# Section_A_-_Title_A.net
KiCad netlist of a schematic drawn in Altium Designer
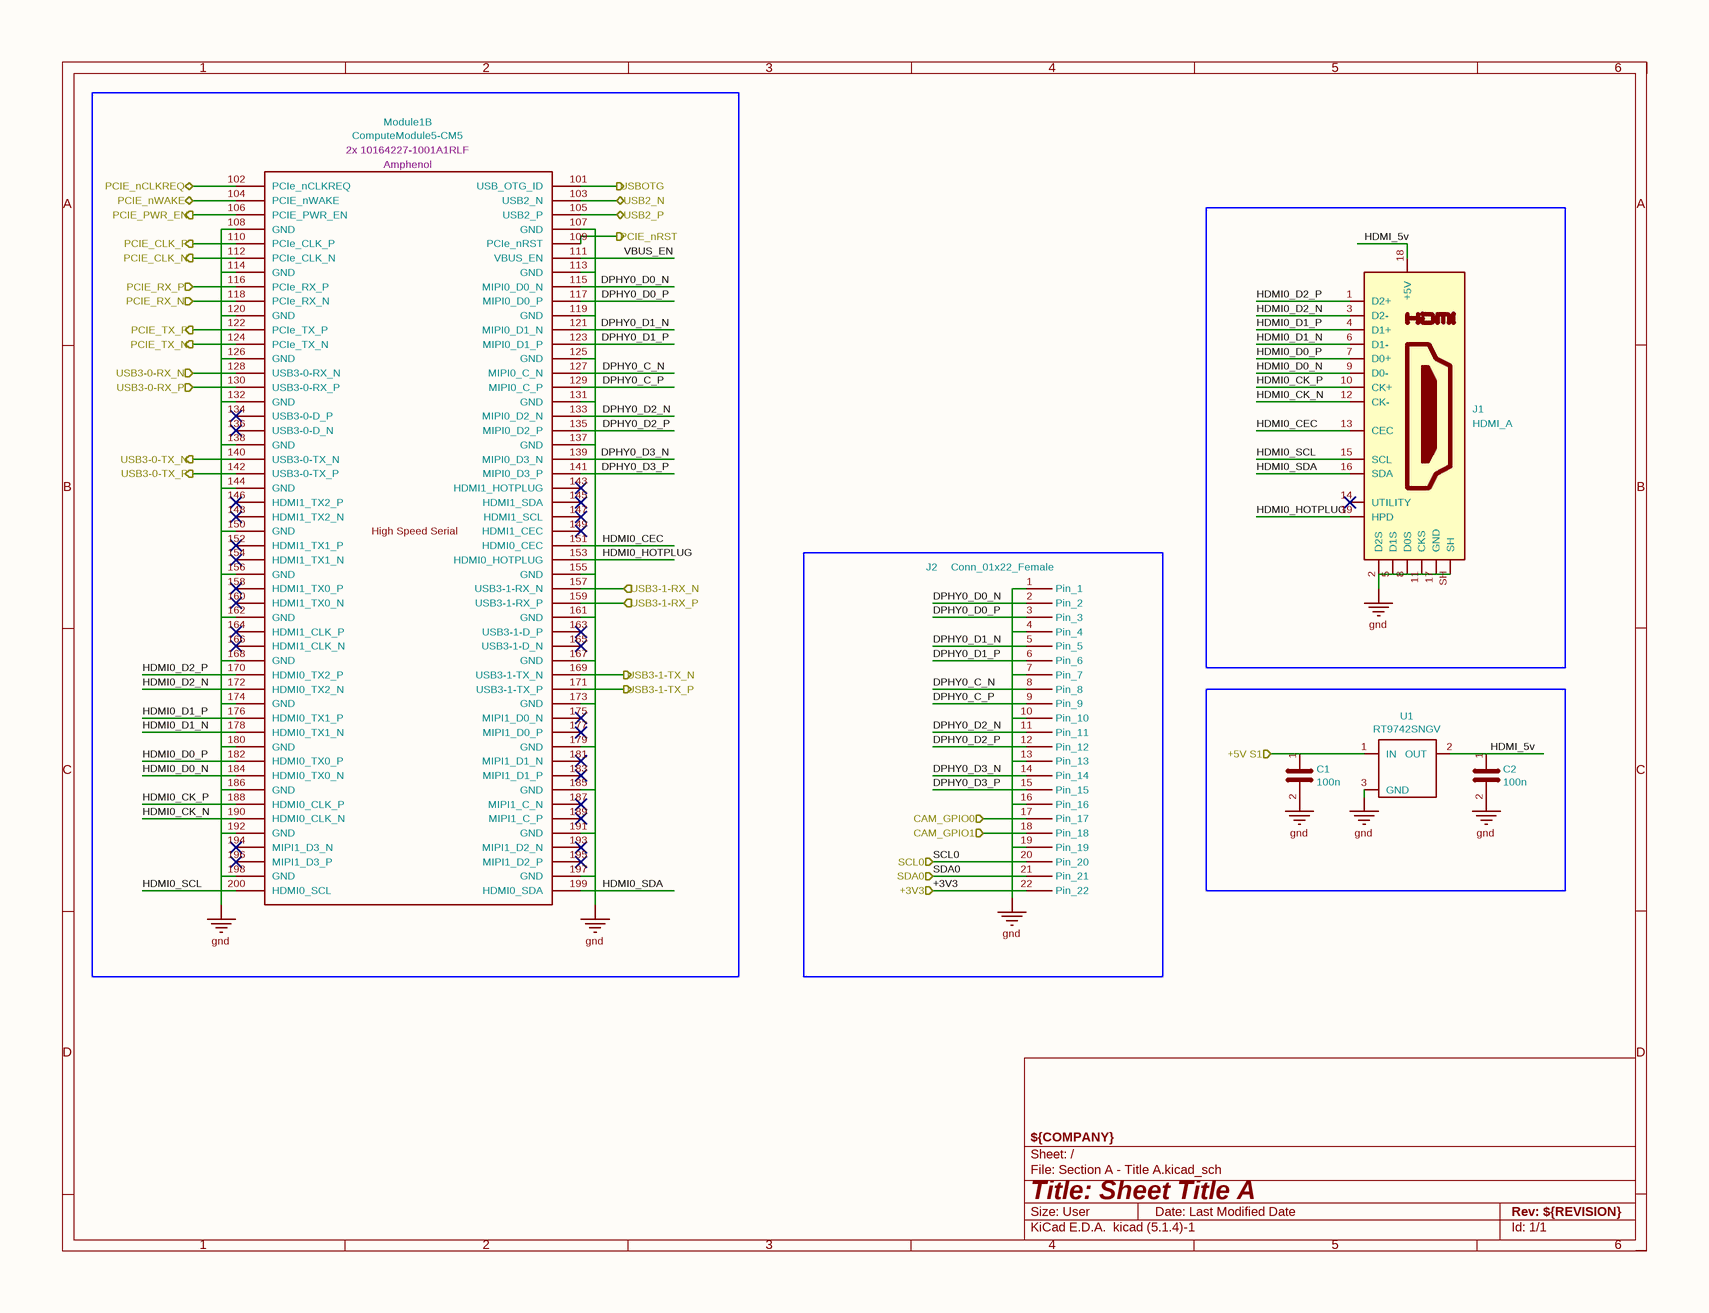
[diagram p0: Section A - Title A.SchDoc]

(export (version "E")
  (design (tool "Eeschema 10.0.6"))
  (components
    (comp (ref "C1") (value "100n") (libsource (lib "Device") (part "C")))
    (comp (ref "C2") (value "100n") (libsource (lib "Device") (part "C")))
    (comp (ref "J1")
      (value "HDMI_A")
      (description "HDMI type A connector")
      (libsource (lib "Connector") (part "HDMI_A"))
    )
    (comp (ref "J2") (value "Conn_01x22_Female") (libsource (lib "Connector") (part "Conn_01x22_Socket")))
    (comp (ref "Module1")
      (value "ComputeModule5-CM5")
      (description "RaspberryPi Compute module 5")
      (fields (field (name "FIELD4") "Amphenol") (field (name "FIELD5") "2x 10164227-1001A1RLF"))
      (libsource (lib "CM5IO") (part "ComputeModule5-CM5"))
    )
    (comp (ref "U1") (value "RT9742SNGV") (libsource (lib "CM5IO") (part "RT9742SNGV")))
  )
  (nets
    (net (code "1") (name "/+3V3") (class "Default")
      (node (ref "J2") (pin "22") (pinfunction "Pin_22_22") (pintype "passive"))
    )
    (net (code "2") (name "/+5V S1") (class "Default")
      (node (ref "C1") (pin "1") (pinfunction "1_1") (pintype "passive"))
      (node (ref "U1") (pin "1") (pinfunction "IN_1") (pintype "passive"))
    )
    (net (code "3") (name "/CAM_GPIO0") (class "Default")
      (node (ref "J2") (pin "17") (pinfunction "Pin_17_17") (pintype "passive"))
    )
    (net (code "4") (name "/CAM_GPIO1") (class "Default")
      (node (ref "J2") (pin "18") (pinfunction "Pin_18_18") (pintype "passive"))
    )
    (net (code "5") (name "/DPHY0_C_N") (class "Default")
      (node (ref "J2") (pin "8") (pinfunction "Pin_8_8") (pintype "passive"))
      (node (ref "Module1") (pin "127") (pinfunction "MIPI0_C_N_127") (pintype "passive"))
    )
    (net (code "6") (name "/DPHY0_C_P") (class "Default")
      (node (ref "J2") (pin "9") (pinfunction "Pin_9_9") (pintype "passive"))
      (node (ref "Module1") (pin "129") (pinfunction "MIPI0_C_P_129") (pintype "passive"))
    )
    (net (code "7") (name "/DPHY0_D0_N") (class "Default")
      (node (ref "J2") (pin "2") (pinfunction "Pin_2_2") (pintype "passive"))
      (node (ref "Module1") (pin "115") (pinfunction "MIPI0_D0_N_115") (pintype "passive"))
    )
    (net (code "8") (name "/DPHY0_D0_P") (class "Default")
      (node (ref "J2") (pin "3") (pinfunction "Pin_3_3") (pintype "passive"))
      (node (ref "Module1") (pin "117") (pinfunction "MIPI0_D0_P_117") (pintype "passive"))
    )
    (net (code "9") (name "/DPHY0_D1_N") (class "Default")
      (node (ref "J2") (pin "5") (pinfunction "Pin_5_5") (pintype "passive"))
      (node (ref "Module1") (pin "121") (pinfunction "MIPI0_D1_N_121") (pintype "passive"))
    )
    (net (code "10") (name "/DPHY0_D1_P") (class "Default")
      (node (ref "J2") (pin "6") (pinfunction "Pin_6_6") (pintype "passive"))
      (node (ref "Module1") (pin "123") (pinfunction "MIPI0_D1_P_123") (pintype "passive"))
    )
    (net (code "11") (name "/DPHY0_D2_N") (class "Default")
      (node (ref "J2") (pin "11") (pinfunction "Pin_11_11") (pintype "passive"))
      (node (ref "Module1") (pin "133") (pinfunction "MIPI0_D2_N_133") (pintype "passive"))
    )
    (net (code "12") (name "/DPHY0_D2_P") (class "Default")
      (node (ref "J2") (pin "12") (pinfunction "Pin_12_12") (pintype "passive"))
      (node (ref "Module1") (pin "135") (pinfunction "MIPI0_D2_P_135") (pintype "passive"))
    )
    (net (code "13") (name "/DPHY0_D3_N") (class "Default")
      (node (ref "J2") (pin "14") (pinfunction "Pin_14_14") (pintype "passive"))
      (node (ref "Module1") (pin "139") (pinfunction "MIPI0_D3_N_139") (pintype "passive"))
    )
    (net (code "14") (name "/DPHY0_D3_P") (class "Default")
      (node (ref "J2") (pin "15") (pinfunction "Pin_15_15") (pintype "passive"))
      (node (ref "Module1") (pin "141") (pinfunction "MIPI0_D3_P_141") (pintype "passive"))
    )
    (net (code "15") (name "/HDMI0_CEC") (class "Default")
      (node (ref "J1") (pin "13") (pinfunction "CEC_13") (pintype "passive"))
      (node (ref "Module1") (pin "151") (pinfunction "HDMI0_CEC_151") (pintype "passive"))
    )
    (net (code "16") (name "/HDMI0_CK_N") (class "Default")
      (node (ref "J1") (pin "12") (pinfunction "CK-_12") (pintype "passive"))
      (node (ref "Module1") (pin "190") (pinfunction "HDMI0_CLK_N_190") (pintype "passive"))
    )
    (net (code "17") (name "/HDMI0_CK_P") (class "Default")
      (node (ref "J1") (pin "10") (pinfunction "CK+_10") (pintype "passive"))
      (node (ref "Module1") (pin "188") (pinfunction "HDMI0_CLK_P_188") (pintype "passive"))
    )
    (net (code "18") (name "/HDMI0_D0_N") (class "Default")
      (node (ref "J1") (pin "9") (pinfunction "D0-_9") (pintype "passive"))
      (node (ref "Module1") (pin "184") (pinfunction "HDMI0_TX0_N_184") (pintype "passive"))
    )
    (net (code "19") (name "/HDMI0_D0_P") (class "Default")
      (node (ref "J1") (pin "7") (pinfunction "D0+_7") (pintype "passive"))
      (node (ref "Module1") (pin "182") (pinfunction "HDMI0_TX0_P_182") (pintype "passive"))
    )
    (net (code "20") (name "/HDMI0_D1_N") (class "Default")
      (node (ref "J1") (pin "6") (pinfunction "D1-_6") (pintype "passive"))
      (node (ref "Module1") (pin "178") (pinfunction "HDMI0_TX1_N_178") (pintype "passive"))
    )
    (net (code "21") (name "/HDMI0_D1_P") (class "Default")
      (node (ref "J1") (pin "4") (pinfunction "D1+_4") (pintype "passive"))
      (node (ref "Module1") (pin "176") (pinfunction "HDMI0_TX1_P_176") (pintype "passive"))
    )
    (net (code "22") (name "/HDMI0_D2_N") (class "Default")
      (node (ref "J1") (pin "3") (pinfunction "D2-_3") (pintype "passive"))
      (node (ref "Module1") (pin "172") (pinfunction "HDMI0_TX2_N_172") (pintype "passive"))
    )
    (net (code "23") (name "/HDMI0_D2_P") (class "Default")
      (node (ref "J1") (pin "1") (pinfunction "D2+_1") (pintype "passive"))
      (node (ref "Module1") (pin "170") (pinfunction "HDMI0_TX2_P_170") (pintype "passive"))
    )
    (net (code "24") (name "/HDMI0_HOTPLUG") (class "Default")
      (node (ref "J1") (pin "19") (pinfunction "HPD_19") (pintype "passive"))
      (node (ref "Module1") (pin "153") (pinfunction "HDMI0_HOTPLUG_153") (pintype "passive"))
    )
    (net (code "25") (name "/HDMI0_SCL") (class "Default")
      (node (ref "J1") (pin "15") (pinfunction "SCL_15") (pintype "passive"))
      (node (ref "Module1") (pin "200") (pinfunction "HDMI0_SCL_200") (pintype "passive"))
    )
    (net (code "26") (name "/HDMI0_SDA") (class "Default")
      (node (ref "J1") (pin "16") (pinfunction "SDA_16") (pintype "passive"))
      (node (ref "Module1") (pin "199") (pinfunction "HDMI0_SDA_199") (pintype "passive"))
    )
    (net (code "27") (name "/HDMI_5v") (class "Default")
      (node (ref "C2") (pin "1") (pinfunction "1_1") (pintype "passive"))
      (node (ref "J1") (pin "18") (pinfunction "+5V_18") (pintype "passive"))
      (node (ref "U1") (pin "2") (pinfunction "OUT_2") (pintype "passive"))
    )
    (net (code "28") (name "/PCIE_CLK_N") (class "Default")
      (node (ref "Module1") (pin "112") (pinfunction "PCIe_CLK_N_112") (pintype "passive"))
    )
    (net (code "29") (name "/PCIE_CLK_P") (class "Default")
      (node (ref "Module1") (pin "110") (pinfunction "PCIe_CLK_P_110") (pintype "passive"))
    )
    (net (code "30") (name "/PCIE_PWR_EN") (class "Default")
      (node (ref "Module1") (pin "106") (pinfunction "PCIE_PWR_EN_106") (pintype "passive"))
    )
    (net (code "31") (name "/PCIE_RX_N") (class "Default")
      (node (ref "Module1") (pin "118") (pinfunction "PCIe_RX_N_118") (pintype "passive"))
    )
    (net (code "32") (name "/PCIE_RX_P") (class "Default")
      (node (ref "Module1") (pin "116") (pinfunction "PCIe_RX_P_116") (pintype "passive"))
    )
    (net (code "33") (name "/PCIE_TX_N") (class "Default")
      (node (ref "Module1") (pin "124") (pinfunction "PCIe_TX_N_124") (pintype "passive"))
    )
    (net (code "34") (name "/PCIE_TX_P") (class "Default")
      (node (ref "Module1") (pin "122") (pinfunction "PCIe_TX_P_122") (pintype "passive"))
    )
    (net (code "35") (name "/PCIE_nCLKREQ") (class "Default")
      (node (ref "Module1") (pin "102") (pinfunction "PCIe_nCLKREQ_102") (pintype "passive"))
    )
    (net (code "36") (name "/PCIE_nRST") (class "Default")
      (node (ref "Module1") (pin "109") (pinfunction "PCIe_nRST_109") (pintype "passive"))
    )
    (net (code "37") (name "/PCIE_nWAKE") (class "Default")
      (node (ref "Module1") (pin "104") (pinfunction "PCIE_nWAKE_104") (pintype "passive"))
    )
    (net (code "38") (name "/SCL0") (class "Default")
      (node (ref "J2") (pin "20") (pinfunction "Pin_20_20") (pintype "passive"))
    )
    (net (code "39") (name "/SDA0") (class "Default")
      (node (ref "J2") (pin "21") (pinfunction "Pin_21_21") (pintype "passive"))
    )
    (net (code "40") (name "/USB2_N") (class "Default")
      (node (ref "Module1") (pin "103") (pinfunction "USB2_N_103") (pintype "passive"))
    )
    (net (code "41") (name "/USB2_P") (class "Default")
      (node (ref "Module1") (pin "105") (pinfunction "USB2_P_105") (pintype "passive"))
    )
    (net (code "42") (name "/USB3-0-RX_N") (class "Default")
      (node (ref "Module1") (pin "128") (pinfunction "USB3-0-RX_N_128") (pintype "passive"))
    )
    (net (code "43") (name "/USB3-0-RX_P") (class "Default")
      (node (ref "Module1") (pin "130") (pinfunction "USB3-0-RX_P_130") (pintype "passive"))
    )
    (net (code "44") (name "/USB3-0-TX_N") (class "Default")
      (node (ref "Module1") (pin "140") (pinfunction "USB3-0-TX_N_140") (pintype "passive"))
    )
    (net (code "45") (name "/USB3-0-TX_P") (class "Default")
      (node (ref "Module1") (pin "142") (pinfunction "USB3-0-TX_P_142") (pintype "passive"))
    )
    (net (code "46") (name "/USB3-1-RX_N") (class "Default")
      (node (ref "Module1") (pin "157") (pinfunction "USB3-1-RX_N_157") (pintype "passive"))
    )
    (net (code "47") (name "/USB3-1-RX_P") (class "Default")
      (node (ref "Module1") (pin "159") (pinfunction "USB3-1-RX_P_159") (pintype "passive"))
    )
    (net (code "48") (name "/USB3-1-TX_N") (class "Default")
      (node (ref "Module1") (pin "169") (pinfunction "USB3-1-TX_N_169") (pintype "passive"))
    )
    (net (code "49") (name "/USB3-1-TX_P") (class "Default")
      (node (ref "Module1") (pin "171") (pinfunction "USB3-1-TX_P_171") (pintype "passive"))
    )
    (net (code "50") (name "/USBOTG") (class "Default")
      (node (ref "Module1") (pin "101") (pinfunction "USB_OTG_ID_101") (pintype "passive"))
    )
    (net (code "51") (name "/VBUS_EN") (class "Default")
      (node (ref "Module1") (pin "111") (pinfunction "VBUS_EN_111") (pintype "passive"))
    )
    (net (code "52") (name "gnd") (class "Default")
      (node (ref "C1") (pin "2") (pinfunction "2_2") (pintype "passive"))
      (node (ref "C2") (pin "2") (pinfunction "2_2") (pintype "passive"))
      (node (ref "J1") (pin "11") (pinfunction "CKS_11") (pintype "passive"))
      (node (ref "J1") (pin "17") (pinfunction "GND_17") (pintype "passive"))
      (node (ref "J1") (pin "2") (pinfunction "D2S_2") (pintype "passive"))
      (node (ref "J1") (pin "5") (pinfunction "D1S_5") (pintype "passive"))
      (node (ref "J1") (pin "8") (pinfunction "D0S_8") (pintype "passive"))
      (node (ref "J1") (pin "SH") (pinfunction "SH_SH") (pintype "passive"))
      (node (ref "J2") (pin "1") (pinfunction "Pin_1_1") (pintype "passive"))
      (node (ref "J2") (pin "10") (pinfunction "Pin_10_10") (pintype "passive"))
      (node (ref "J2") (pin "13") (pinfunction "Pin_13_13") (pintype "passive"))
      (node (ref "J2") (pin "16") (pinfunction "Pin_16_16") (pintype "passive"))
      (node (ref "J2") (pin "19") (pinfunction "Pin_19_19") (pintype "passive"))
      (node (ref "J2") (pin "4") (pinfunction "Pin_4_4") (pintype "passive"))
      (node (ref "J2") (pin "7") (pinfunction "Pin_7_7") (pintype "passive"))
      (node (ref "Module1") (pin "107") (pinfunction "GND_107") (pintype "passive"))
      (node (ref "Module1") (pin "108") (pinfunction "GND_108") (pintype "passive"))
      (node (ref "Module1") (pin "113") (pinfunction "GND_113") (pintype "passive"))
      (node (ref "Module1") (pin "114") (pinfunction "GND_114") (pintype "passive"))
      (node (ref "Module1") (pin "119") (pinfunction "GND_119") (pintype "passive"))
      (node (ref "Module1") (pin "120") (pinfunction "GND_120") (pintype "passive"))
      (node (ref "Module1") (pin "125") (pinfunction "GND_125") (pintype "passive"))
      (node (ref "Module1") (pin "126") (pinfunction "GND_126") (pintype "passive"))
      (node (ref "Module1") (pin "131") (pinfunction "GND_131") (pintype "passive"))
      (node (ref "Module1") (pin "132") (pinfunction "GND_132") (pintype "passive"))
      (node (ref "Module1") (pin "137") (pinfunction "GND_137") (pintype "passive"))
      (node (ref "Module1") (pin "138") (pinfunction "GND_138") (pintype "passive"))
      (node (ref "Module1") (pin "144") (pinfunction "GND_144") (pintype "passive"))
      (node (ref "Module1") (pin "150") (pinfunction "GND_150") (pintype "passive"))
      (node (ref "Module1") (pin "155") (pinfunction "GND_155") (pintype "passive"))
      (node (ref "Module1") (pin "156") (pinfunction "GND_156") (pintype "passive"))
      (node (ref "Module1") (pin "161") (pinfunction "GND_161") (pintype "passive"))
      (node (ref "Module1") (pin "162") (pinfunction "GND_162") (pintype "passive"))
      (node (ref "Module1") (pin "167") (pinfunction "GND_167") (pintype "passive"))
      (node (ref "Module1") (pin "168") (pinfunction "GND_168") (pintype "passive"))
      (node (ref "Module1") (pin "173") (pinfunction "GND_173") (pintype "passive"))
      (node (ref "Module1") (pin "174") (pinfunction "GND_174") (pintype "passive"))
      (node (ref "Module1") (pin "179") (pinfunction "GND_179") (pintype "passive"))
      (node (ref "Module1") (pin "180") (pinfunction "GND_180") (pintype "passive"))
      (node (ref "Module1") (pin "185") (pinfunction "GND_185") (pintype "passive"))
      (node (ref "Module1") (pin "186") (pinfunction "GND_186") (pintype "passive"))
      (node (ref "Module1") (pin "191") (pinfunction "GND_191") (pintype "passive"))
      (node (ref "Module1") (pin "192") (pinfunction "GND_192") (pintype "passive"))
      (node (ref "Module1") (pin "197") (pinfunction "GND_197") (pintype "passive"))
      (node (ref "Module1") (pin "198") (pinfunction "GND_198") (pintype "passive"))
      (node (ref "U1") (pin "3") (pinfunction "GND_3") (pintype "passive"))
    )
    (net (code "53") (name "unconnected-(J1-UTILITY-Pad14)") (class "Default")
      (node (ref "J1") (pin "14") (pinfunction "UTILITY_14") (pintype "passive+no_connect"))
    )
    (net (code "54") (name "unconnected-(Module1B-HDMI1_CEC-Pad149)") (class "Default")
      (node (ref "Module1") (pin "149") (pinfunction "HDMI1_CEC_149") (pintype "passive+no_connect"))
    )
    (net (code "55") (name "unconnected-(Module1B-HDMI1_CLK_N-Pad166)") (class "Default")
      (node (ref "Module1") (pin "166") (pinfunction "HDMI1_CLK_N_166") (pintype "passive+no_connect"))
    )
    (net (code "56") (name "unconnected-(Module1B-HDMI1_CLK_P-Pad164)") (class "Default")
      (node (ref "Module1") (pin "164") (pinfunction "HDMI1_CLK_P_164") (pintype "passive+no_connect"))
    )
    (net (code "57") (name "unconnected-(Module1B-HDMI1_HOTPLUG-Pad143)") (class "Default")
      (node (ref "Module1") (pin "143") (pinfunction "HDMI1_HOTPLUG_143") (pintype "passive+no_connect"))
    )
    (net (code "58") (name "unconnected-(Module1B-HDMI1_SCL-Pad147)") (class "Default")
      (node (ref "Module1") (pin "147") (pinfunction "HDMI1_SCL_147") (pintype "passive+no_connect"))
    )
    (net (code "59") (name "unconnected-(Module1B-HDMI1_SDA-Pad145)") (class "Default")
      (node (ref "Module1") (pin "145") (pinfunction "HDMI1_SDA_145") (pintype "passive+no_connect"))
    )
    (net (code "60") (name "unconnected-(Module1B-HDMI1_TX0_N-Pad160)") (class "Default")
      (node (ref "Module1") (pin "160") (pinfunction "HDMI1_TX0_N_160") (pintype "passive+no_connect"))
    )
    (net (code "61") (name "unconnected-(Module1B-HDMI1_TX0_P-Pad158)") (class "Default")
      (node (ref "Module1") (pin "158") (pinfunction "HDMI1_TX0_P_158") (pintype "passive+no_connect"))
    )
    (net (code "62") (name "unconnected-(Module1B-HDMI1_TX1_N-Pad154)") (class "Default")
      (node (ref "Module1") (pin "154") (pinfunction "HDMI1_TX1_N_154") (pintype "passive+no_connect"))
    )
    (net (code "63") (name "unconnected-(Module1B-HDMI1_TX1_P-Pad152)") (class "Default")
      (node (ref "Module1") (pin "152") (pinfunction "HDMI1_TX1_P_152") (pintype "passive+no_connect"))
    )
    (net (code "64") (name "unconnected-(Module1B-HDMI1_TX2_N-Pad148)") (class "Default")
      (node (ref "Module1") (pin "148") (pinfunction "HDMI1_TX2_N_148") (pintype "passive+no_connect"))
    )
    (net (code "65") (name "unconnected-(Module1B-HDMI1_TX2_P-Pad146)") (class "Default")
      (node (ref "Module1") (pin "146") (pinfunction "HDMI1_TX2_P_146") (pintype "passive+no_connect"))
    )
    (net (code "66") (name "unconnected-(Module1B-MIPI1_C_N-Pad187)") (class "Default")
      (node (ref "Module1") (pin "187") (pinfunction "MIPI1_C_N_187") (pintype "passive+no_connect"))
    )
    (net (code "67") (name "unconnected-(Module1B-MIPI1_C_P-Pad189)") (class "Default")
      (node (ref "Module1") (pin "189") (pinfunction "MIPI1_C_P_189") (pintype "passive+no_connect"))
    )
    (net (code "68") (name "unconnected-(Module1B-MIPI1_D0_N-Pad175)") (class "Default")
      (node (ref "Module1") (pin "175") (pinfunction "MIPI1_D0_N_175") (pintype "passive+no_connect"))
    )
    (net (code "69") (name "unconnected-(Module1B-MIPI1_D0_P-Pad177)") (class "Default")
      (node (ref "Module1") (pin "177") (pinfunction "MIPI1_D0_P_177") (pintype "passive+no_connect"))
    )
    (net (code "70") (name "unconnected-(Module1B-MIPI1_D1_N-Pad181)") (class "Default")
      (node (ref "Module1") (pin "181") (pinfunction "MIPI1_D1_N_181") (pintype "passive+no_connect"))
    )
    (net (code "71") (name "unconnected-(Module1B-MIPI1_D1_P-Pad183)") (class "Default")
      (node (ref "Module1") (pin "183") (pinfunction "MIPI1_D1_P_183") (pintype "passive+no_connect"))
    )
    (net (code "72") (name "unconnected-(Module1B-MIPI1_D2_N-Pad193)") (class "Default")
      (node (ref "Module1") (pin "193") (pinfunction "MIPI1_D2_N_193") (pintype "passive+no_connect"))
    )
    (net (code "73") (name "unconnected-(Module1B-MIPI1_D2_P-Pad195)") (class "Default")
      (node (ref "Module1") (pin "195") (pinfunction "MIPI1_D2_P_195") (pintype "passive+no_connect"))
    )
    (net (code "74") (name "unconnected-(Module1B-MIPI1_D3_N-Pad194)") (class "Default")
      (node (ref "Module1") (pin "194") (pinfunction "MIPI1_D3_N_194") (pintype "passive+no_connect"))
    )
    (net (code "75") (name "unconnected-(Module1B-MIPI1_D3_P-Pad196)") (class "Default")
      (node (ref "Module1") (pin "196") (pinfunction "MIPI1_D3_P_196") (pintype "passive+no_connect"))
    )
    (net (code "76") (name "unconnected-(Module1B-USB3-0-D_N-Pad136)") (class "Default")
      (node (ref "Module1") (pin "136") (pinfunction "USB3-0-D_N_136") (pintype "passive+no_connect"))
    )
    (net (code "77") (name "unconnected-(Module1B-USB3-0-D_P-Pad134)") (class "Default")
      (node (ref "Module1") (pin "134") (pinfunction "USB3-0-D_P_134") (pintype "passive+no_connect"))
    )
    (net (code "78") (name "unconnected-(Module1B-USB3-1-D_N-Pad165)") (class "Default")
      (node (ref "Module1") (pin "165") (pinfunction "USB3-1-D_N_165") (pintype "passive+no_connect"))
    )
    (net (code "79") (name "unconnected-(Module1B-USB3-1-D_P-Pad163)") (class "Default")
      (node (ref "Module1") (pin "163") (pinfunction "USB3-1-D_P_163") (pintype "passive+no_connect"))
    )
  )
)
